# SolarCellY_v2_6milmag.net
KiCad netlist of a schematic drawn in EAGLE
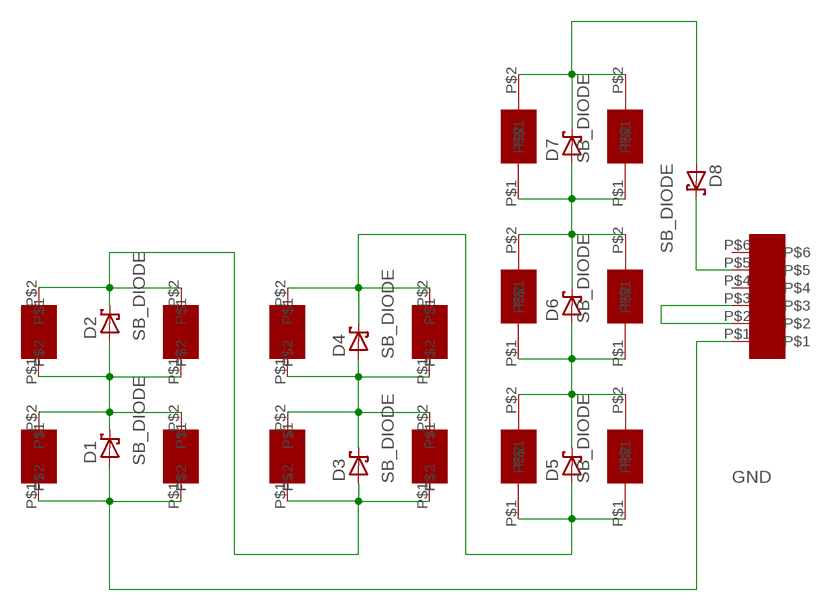
[diagram p0: schematic, sheet 1]

(export (version "E")
  (design (tool "Eeschema 10.0.6"))
  (components
    (comp (ref "11")
      (value "SLMD121H04L")
      (footprint "eagle-import:SLMD121H04L")
      (libsource (lib "eagle-import") (part "SLMD121H04L"))
    )
    (comp (ref "12")
      (value "SLMD121H04L")
      (footprint "eagle-import:SLMD121H04L")
      (libsource (lib "eagle-import") (part "SLMD121H04L"))
    )
    (comp (ref "13")
      (value "SLMD121H04L")
      (footprint "eagle-import:SLMD121H04L")
      (libsource (lib "eagle-import") (part "SLMD121H04L"))
    )
    (comp (ref "14")
      (value "SLMD121H04L")
      (footprint "eagle-import:SLMD121H04L")
      (libsource (lib "eagle-import") (part "SLMD121H04L"))
    )
    (comp (ref "21")
      (value "SLMD121H04L")
      (footprint "eagle-import:SLMD121H04L")
      (libsource (lib "eagle-import") (part "SLMD121H04L"))
    )
    (comp (ref "22")
      (value "SLMD121H04L")
      (footprint "eagle-import:SLMD121H04L")
      (libsource (lib "eagle-import") (part "SLMD121H04L"))
    )
    (comp (ref "23")
      (value "SLMD121H04L")
      (footprint "eagle-import:SLMD121H04L")
      (libsource (lib "eagle-import") (part "SLMD121H04L"))
    )
    (comp (ref "24")
      (value "SLMD121H04L")
      (footprint "eagle-import:SLMD121H04L")
      (libsource (lib "eagle-import") (part "SLMD121H04L"))
    )
    (comp (ref "D1")
      (value "SB_DIODE")
      (footprint "eagle-import:SB_DIODE")
      (libsource (lib "eagle-import") (part "SB_DIODE"))
    )
    (comp (ref "D2")
      (value "SB_DIODE")
      (footprint "eagle-import:SB_DIODE")
      (libsource (lib "eagle-import") (part "SB_DIODE"))
    )
    (comp (ref "D3")
      (value "SB_DIODE")
      (footprint "eagle-import:SB_DIODE")
      (libsource (lib "eagle-import") (part "SB_DIODE"))
    )
    (comp (ref "D4")
      (value "SB_DIODE")
      (footprint "eagle-import:SB_DIODE")
      (libsource (lib "eagle-import") (part "SB_DIODE"))
    )
    (comp (ref "D5")
      (value "SB_DIODE")
      (footprint "eagle-import:SB_DIODE")
      (libsource (lib "eagle-import") (part "SB_DIODE"))
    )
    (comp (ref "D6")
      (value "SB_DIODE")
      (footprint "eagle-import:SB_DIODE")
      (libsource (lib "eagle-import") (part "SB_DIODE"))
    )
    (comp (ref "D7")
      (value "SB_DIODE")
      (footprint "eagle-import:SB_DIODE")
      (libsource (lib "eagle-import") (part "SB_DIODE"))
    )
    (comp (ref "D8")
      (value "SB_DIODE")
      (footprint "eagle-import:SB_DIODE")
      (libsource (lib "eagle-import") (part "SB_DIODE"))
    )
    (comp (ref "U$1")
      (value "M20-8760342")
      (footprint "eagle-import:M20-8760342")
      (libsource (lib "eagle-import") (part "M20-8760342"))
    )
    (comp (ref "U$2")
      (value "KXOB22-04X3F")
      (footprint "eagle-import:KXOB22-04X3F")
      (libsource (lib "eagle-import") (part "KXOB22-04X3F"))
    )
    (comp (ref "U$3")
      (value "KXOB22-04X3F")
      (footprint "eagle-import:KXOB22-04X3F")
      (libsource (lib "eagle-import") (part "KXOB22-04X3F"))
    )
    (comp (ref "U$4")
      (value "KXOB22-04X3F")
      (footprint "eagle-import:KXOB22-04X3F")
      (libsource (lib "eagle-import") (part "KXOB22-04X3F"))
    )
    (comp (ref "U$5")
      (value "KXOB22-04X3F")
      (footprint "eagle-import:KXOB22-04X3F")
      (libsource (lib "eagle-import") (part "KXOB22-04X3F"))
    )
    (comp (ref "U$6")
      (value "KXOB22-04X3F")
      (footprint "eagle-import:KXOB22-04X3F")
      (libsource (lib "eagle-import") (part "KXOB22-04X3F"))
    )
    (comp (ref "U$7")
      (value "KXOB22-04X3F")
      (footprint "eagle-import:KXOB22-04X3F")
      (libsource (lib "eagle-import") (part "KXOB22-04X3F"))
    )
  )
  (nets
    (net (code "1") (name "/GND") (class "Default")
      (node (ref "11") (pin "P$1") (pinfunction "P$1_P$1") (pintype "bidirectional"))
      (node (ref "12") (pin "P$1") (pinfunction "P$1_P$1") (pintype "bidirectional"))
      (node (ref "D1") (pin "POS") (pinfunction "POS_POS") (pintype "passive"))
      (node (ref "U$1") (pin "P$1") (pinfunction "P$1_P$1") (pintype "bidirectional"))
    )
    (net (code "2") (name "Net-(11-PadP$2)") (class "Default")
      (node (ref "11") (pin "P$2") (pinfunction "P$2_P$2") (pintype "bidirectional"))
      (node (ref "12") (pin "P$2") (pinfunction "P$2_P$2") (pintype "bidirectional"))
      (node (ref "13") (pin "P$1") (pinfunction "P$1_P$1") (pintype "bidirectional"))
      (node (ref "14") (pin "P$1") (pinfunction "P$1_P$1") (pintype "bidirectional"))
      (node (ref "D1") (pin "NEG") (pinfunction "NEG_NEG") (pintype "passive"))
      (node (ref "D2") (pin "POS") (pinfunction "POS_POS") (pintype "passive"))
    )
    (net (code "3") (name "Net-(13-PadP$2)") (class "Default")
      (node (ref "13") (pin "P$2") (pinfunction "P$2_P$2") (pintype "bidirectional"))
      (node (ref "14") (pin "P$2") (pinfunction "P$2_P$2") (pintype "bidirectional"))
      (node (ref "21") (pin "P$1") (pinfunction "P$1_P$1") (pintype "bidirectional"))
      (node (ref "22") (pin "P$1") (pinfunction "P$1_P$1") (pintype "bidirectional"))
      (node (ref "D2") (pin "NEG") (pinfunction "NEG_NEG") (pintype "passive"))
      (node (ref "D3") (pin "POS") (pinfunction "POS_POS") (pintype "passive"))
    )
    (net (code "4") (name "Net-(21-PadP$2)") (class "Default")
      (node (ref "21") (pin "P$2") (pinfunction "P$2_P$2") (pintype "bidirectional"))
      (node (ref "22") (pin "P$2") (pinfunction "P$2_P$2") (pintype "bidirectional"))
      (node (ref "23") (pin "P$1") (pinfunction "P$1_P$1") (pintype "bidirectional"))
      (node (ref "24") (pin "P$1") (pinfunction "P$1_P$1") (pintype "bidirectional"))
      (node (ref "D3") (pin "NEG") (pinfunction "NEG_NEG") (pintype "passive"))
      (node (ref "D4") (pin "POS") (pinfunction "POS_POS") (pintype "passive"))
    )
    (net (code "5") (name "Net-(23-PadP$2)") (class "Default")
      (node (ref "23") (pin "P$2") (pinfunction "P$2_P$2") (pintype "bidirectional"))
      (node (ref "24") (pin "P$2") (pinfunction "P$2_P$2") (pintype "bidirectional"))
      (node (ref "D4") (pin "NEG") (pinfunction "NEG_NEG") (pintype "passive"))
      (node (ref "D5") (pin "POS") (pinfunction "POS_POS") (pintype "passive"))
      (node (ref "U$2") (pin "P$1") (pinfunction "P$1_P$1") (pintype "bidirectional"))
      (node (ref "U$3") (pin "P$1") (pinfunction "P$1_P$1") (pintype "bidirectional"))
    )
    (net (code "6") (name "Net-(D5-PadNEG)") (class "Default")
      (node (ref "D5") (pin "NEG") (pinfunction "NEG_NEG") (pintype "passive"))
      (node (ref "D6") (pin "POS") (pinfunction "POS_POS") (pintype "passive"))
      (node (ref "U$2") (pin "P$2") (pinfunction "P$2_P$2") (pintype "bidirectional"))
      (node (ref "U$3") (pin "P$2") (pinfunction "P$2_P$2") (pintype "bidirectional"))
      (node (ref "U$4") (pin "P$1") (pinfunction "P$1_P$1") (pintype "bidirectional"))
      (node (ref "U$5") (pin "P$1") (pinfunction "P$1_P$1") (pintype "bidirectional"))
    )
    (net (code "7") (name "Net-(D6-PadNEG)") (class "Default")
      (node (ref "D6") (pin "NEG") (pinfunction "NEG_NEG") (pintype "passive"))
      (node (ref "D7") (pin "POS") (pinfunction "POS_POS") (pintype "passive"))
      (node (ref "U$4") (pin "P$2") (pinfunction "P$2_P$2") (pintype "bidirectional"))
      (node (ref "U$5") (pin "P$2") (pinfunction "P$2_P$2") (pintype "bidirectional"))
      (node (ref "U$6") (pin "P$1") (pinfunction "P$1_P$1") (pintype "bidirectional"))
      (node (ref "U$7") (pin "P$1") (pinfunction "P$1_P$1") (pintype "bidirectional"))
    )
    (net (code "8") (name "Net-(D7-PadNEG)") (class "Default")
      (node (ref "D7") (pin "NEG") (pinfunction "NEG_NEG") (pintype "passive"))
      (node (ref "D8") (pin "POS") (pinfunction "POS_POS") (pintype "passive"))
      (node (ref "U$6") (pin "P$2") (pinfunction "P$2_P$2") (pintype "bidirectional"))
      (node (ref "U$7") (pin "P$2") (pinfunction "P$2_P$2") (pintype "bidirectional"))
    )
    (net (code "9") (name "Net-(D8-PadNEG)") (class "Default")
      (node (ref "D8") (pin "NEG") (pinfunction "NEG_NEG") (pintype "passive"))
      (node (ref "U$1") (pin "P$5") (pinfunction "P$5_P$5") (pintype "bidirectional"))
    )
    (net (code "10") (name "Net-(U$1-PadP$2)") (class "Default")
      (node (ref "U$1") (pin "P$2") (pinfunction "P$2_P$2") (pintype "bidirectional"))
      (node (ref "U$1") (pin "P$3") (pinfunction "P$3_P$3") (pintype "bidirectional"))
    )
    (net (code "11") (name "unconnected-(U$1-PadP$4)") (class "Default")
      (node (ref "U$1") (pin "P$4") (pinfunction "P$4_P$4") (pintype "bidirectional"))
    )
    (net (code "12") (name "unconnected-(U$1-PadP$6)") (class "Default")
      (node (ref "U$1") (pin "P$6") (pinfunction "P$6_P$6") (pintype "bidirectional"))
    )
  )
)
